# Model_v1_0.net
KiCad netlist of a schematic drawn in Altium Designer
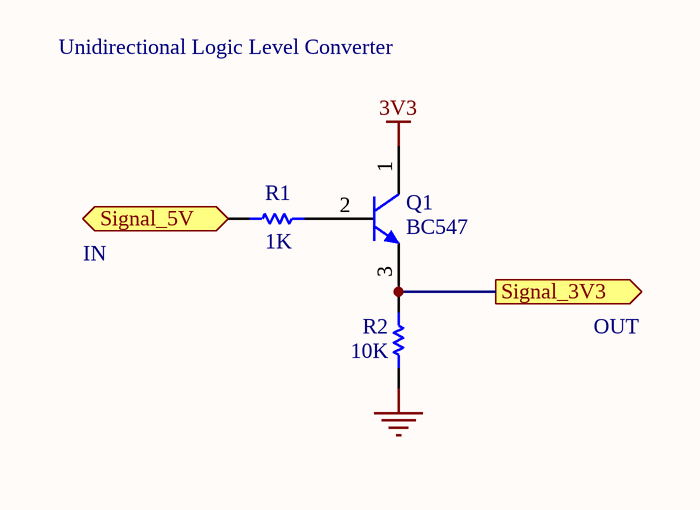
[diagram p0: Model_v1.0.SchDoc]

(export (version "E")
  (design (tool "Eeschema 10.0.6"))
  (components
    (comp (ref "Q1")
      (value "BC547")
      (footprint "TO92_3Pin")
      (description "Transistor, BJT, NPN")
      (libsource (lib "General") (part "Transistor_BJT_NPN_cbe"))
    )
    (comp (ref "R1")
      (value "1K")
      (footprint "SMD_0805")
      (description "Resistor, 1/4W, 5%")
      (libsource (lib "") (part "Resistor_1"))
    )
    (comp (ref "R2")
      (value "10K")
      (footprint "SMD_0805")
      (description "Resistor, 1/4W, 5%")
      (libsource (lib "General") (part "Resistor"))
    )
  )
  (nets
    (net (code "1") (name "/Signal_3V3") (class "Default")
      (node (ref "Q1") (pin "3") (pinfunction "E_3") (pintype "passive"))
      (node (ref "R2") (pin "2") (pinfunction "2_2") (pintype "passive"))
    )
    (net (code "2") (name "/Signal_5V") (class "Default")
      (node (ref "R1") (pin "2") (pinfunction "2_2") (pintype "passive"))
    )
    (net (code "3") (name "3V3") (class "Default")
      (node (ref "Q1") (pin "1") (pinfunction "C_1") (pintype "passive"))
    )
    (net (code "4") (name "GND") (class "Default")
      (node (ref "R2") (pin "1") (pinfunction "1_1") (pintype "passive"))
    )
    (net (code "5") (name "Net-(Q1-B)") (class "Default")
      (node (ref "Q1") (pin "2") (pinfunction "B_2") (pintype "passive"))
      (node (ref "R1") (pin "1") (pinfunction "1_1") (pintype "passive"))
    )
  )
)
